# BUFFER.net
KiCad netlist of a schematic drawn in Altium Designer
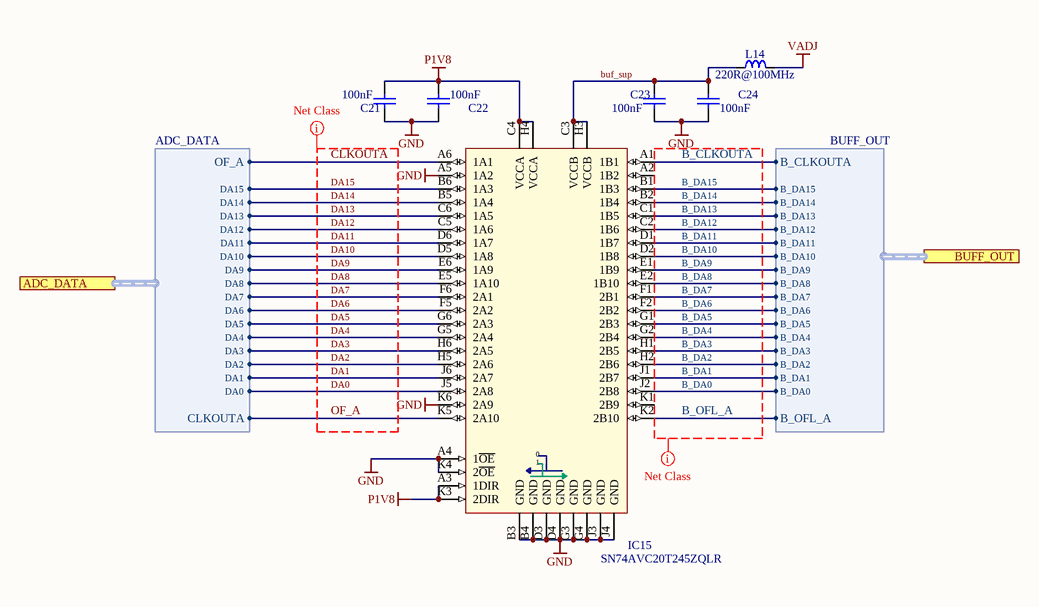
[diagram p0: BUFFER.SchDoc]

(export (version "E")
  (design (tool "Eeschema 10.0.6"))
  (components
    (comp (ref "C21")
      (value "100nF")
      (footprint "CAPC0603X33N")
      (description "Non-polarised capacitor")
      (fields
        (field (name "PART NUMBER") "CC0201_100NF_6.3V_10%_X5R")
        (field (name "VOLTAGE") "6.3V")
        (field (name "AUTHOR") "CERN DEM JLC")
      )
      (libsource (lib "Capacitors") (part "Capacitor - non polarized"))
    )
    (comp (ref "C22")
      (value "100nF")
      (footprint "CAPC0603X33N")
      (description "Non-polarised capacitor")
      (fields
        (field (name "PART NUMBER") "CC0201_100NF_6.3V_10%_X5R")
        (field (name "VOLTAGE") "6.3V")
        (field (name "AUTHOR") "CERN DEM JLC")
      )
      (libsource (lib "Capacitors") (part "Capacitor - non polarized"))
    )
    (comp (ref "C23")
      (value "100nF")
      (footprint "CAPC0603X33N")
      (description "Non-polarised capacitor")
      (fields
        (field (name "PART NUMBER") "CC0201_100NF_6.3V_10%_X5R")
        (field (name "VOLTAGE") "6.3V")
        (field (name "AUTHOR") "CERN DEM JLC")
      )
      (libsource (lib "Capacitors") (part "Capacitor - non polarized"))
    )
    (comp (ref "C24")
      (value "100nF")
      (footprint "CAPC0603X33N")
      (description "Non-polarised capacitor")
      (fields
        (field (name "PART NUMBER") "CC0201_100NF_6.3V_10%_X5R")
        (field (name "VOLTAGE") "6.3V")
        (field (name "AUTHOR") "CERN DEM JLC")
      )
      (libsource (lib "Capacitors") (part "Capacitor - non polarized"))
    )
    (comp (ref "IC15")
      (value "SN74AVC20T245ZQLR")
      (footprint "ZQL56(R-PBGA-N56)")
      (description "20-BIT DUAL SUPPLY BUS TRANSCEIVER")
      (libsource (lib "LIBRARY_SCH") (part "74AVC20T245"))
    )
    (comp (ref "L14")
      (value "220R@100MHz")
      (footprint "INDC2012X105N")
      (description "Inductor")
      (fields
        (field (name "PART NUMBER") "IND0805_MURATA_BLM21PG221SN1D")
        (field (name "POWER") "2A")
        (field (name "AUTHOR") "CERN DEM JLC")
      )
      (libsource (lib "Inductors & Transformers") (part "Inductor"))
    )
  )
  (nets
    (net (code "3") (name "/B_CLKOUTA") (class "Default")
      (node (ref "IC15") (pin "A1") (pinfunction "1B1_A1") (pintype "bidirectional"))
    )
    (net (code "4") (name "/B_DA0") (class "Default")
      (node (ref "IC15") (pin "J2") (pinfunction "2B8_J2") (pintype "bidirectional"))
    )
    (net (code "5") (name "/B_DA1") (class "Default")
      (node (ref "IC15") (pin "J1") (pinfunction "2B7_J1") (pintype "bidirectional"))
    )
    (net (code "6") (name "/B_DA2") (class "Default")
      (node (ref "IC15") (pin "H2") (pinfunction "2B6_H2") (pintype "bidirectional"))
    )
    (net (code "7") (name "/B_DA3") (class "Default")
      (node (ref "IC15") (pin "H1") (pinfunction "2B5_H1") (pintype "bidirectional"))
    )
    (net (code "8") (name "/B_DA4") (class "Default")
      (node (ref "IC15") (pin "G2") (pinfunction "2B4_G2") (pintype "bidirectional"))
    )
    (net (code "9") (name "/B_DA5") (class "Default")
      (node (ref "IC15") (pin "G1") (pinfunction "2B3_G1") (pintype "bidirectional"))
    )
    (net (code "10") (name "/B_DA6") (class "Default")
      (node (ref "IC15") (pin "F2") (pinfunction "2B2_F2") (pintype "bidirectional"))
    )
    (net (code "11") (name "/B_DA7") (class "Default")
      (node (ref "IC15") (pin "F1") (pinfunction "2B1_F1") (pintype "bidirectional"))
    )
    (net (code "12") (name "/B_DA8") (class "Default")
      (node (ref "IC15") (pin "E2") (pinfunction "1B10_E2") (pintype "bidirectional"))
    )
    (net (code "13") (name "/B_DA9") (class "Default")
      (node (ref "IC15") (pin "E1") (pinfunction "1B9_E1") (pintype "bidirectional"))
    )
    (net (code "14") (name "/B_DA10") (class "Default")
      (node (ref "IC15") (pin "D2") (pinfunction "1B8_D2") (pintype "bidirectional"))
    )
    (net (code "15") (name "/B_DA11") (class "Default")
      (node (ref "IC15") (pin "D1") (pinfunction "1B7_D1") (pintype "bidirectional"))
    )
    (net (code "16") (name "/B_DA12") (class "Default")
      (node (ref "IC15") (pin "C2") (pinfunction "1B6_C2") (pintype "bidirectional"))
    )
    (net (code "17") (name "/B_DA13") (class "Default")
      (node (ref "IC15") (pin "C1") (pinfunction "1B5_C1") (pintype "bidirectional"))
    )
    (net (code "18") (name "/B_DA14") (class "Default")
      (node (ref "IC15") (pin "B2") (pinfunction "1B4_B2") (pintype "bidirectional"))
    )
    (net (code "19") (name "/B_DA15") (class "Default")
      (node (ref "IC15") (pin "B1") (pinfunction "1B3_B1") (pintype "bidirectional"))
    )
    (net (code "20") (name "/B_OFL_A") (class "Default")
      (node (ref "IC15") (pin "K2") (pinfunction "2B10_K2") (pintype "bidirectional"))
    )
    (net (code "21") (name "/CLKOUTA") (class "Default")
      (node (ref "IC15") (pin "A6") (pinfunction "1A1_A6") (pintype "bidirectional"))
    )
    (net (code "22") (name "/DA0") (class "Default")
      (node (ref "IC15") (pin "J5") (pinfunction "2A8_J5") (pintype "bidirectional"))
    )
    (net (code "23") (name "/DA1") (class "Default")
      (node (ref "IC15") (pin "J6") (pinfunction "2A7_J6") (pintype "bidirectional"))
    )
    (net (code "24") (name "/DA2") (class "Default")
      (node (ref "IC15") (pin "H5") (pinfunction "2A6_H5") (pintype "bidirectional"))
    )
    (net (code "25") (name "/DA3") (class "Default")
      (node (ref "IC15") (pin "H6") (pinfunction "2A5_H6") (pintype "bidirectional"))
    )
    (net (code "26") (name "/DA4") (class "Default")
      (node (ref "IC15") (pin "G5") (pinfunction "2A4_G5") (pintype "bidirectional"))
    )
    (net (code "27") (name "/DA5") (class "Default")
      (node (ref "IC15") (pin "G6") (pinfunction "2A3_G6") (pintype "bidirectional"))
    )
    (net (code "28") (name "/DA6") (class "Default")
      (node (ref "IC15") (pin "F5") (pinfunction "2A2_F5") (pintype "bidirectional"))
    )
    (net (code "29") (name "/DA7") (class "Default")
      (node (ref "IC15") (pin "F6") (pinfunction "2A1_F6") (pintype "bidirectional"))
    )
    (net (code "30") (name "/DA8") (class "Default")
      (node (ref "IC15") (pin "E5") (pinfunction "1A10_E5") (pintype "bidirectional"))
    )
    (net (code "31") (name "/DA9") (class "Default")
      (node (ref "IC15") (pin "E6") (pinfunction "1A9_E6") (pintype "bidirectional"))
    )
    (net (code "32") (name "/DA10") (class "Default")
      (node (ref "IC15") (pin "D5") (pinfunction "1A8_D5") (pintype "bidirectional"))
    )
    (net (code "33") (name "/DA11") (class "Default")
      (node (ref "IC15") (pin "D6") (pinfunction "1A7_D6") (pintype "bidirectional"))
    )
    (net (code "34") (name "/DA12") (class "Default")
      (node (ref "IC15") (pin "C5") (pinfunction "1A6_C5") (pintype "bidirectional"))
    )
    (net (code "35") (name "/DA13") (class "Default")
      (node (ref "IC15") (pin "C6") (pinfunction "1A5_C6") (pintype "bidirectional"))
    )
    (net (code "36") (name "/DA14") (class "Default")
      (node (ref "IC15") (pin "B5") (pinfunction "1A4_B5") (pintype "bidirectional"))
    )
    (net (code "37") (name "/DA15") (class "Default")
      (node (ref "IC15") (pin "B6") (pinfunction "1A3_B6") (pintype "bidirectional"))
    )
    (net (code "38") (name "/OF_A") (class "Default")
      (node (ref "IC15") (pin "K5") (pinfunction "2A10_K5") (pintype "bidirectional"))
    )
    (net (code "39") (name "/buf_sup") (class "Default")
      (node (ref "C23") (pin "2") (pinfunction "2_2") (pintype "passive"))
      (node (ref "C24") (pin "2") (pinfunction "2_2") (pintype "passive"))
      (node (ref "IC15") (pin "C3") (pinfunction "VCCB_C3") (pintype "power_in"))
      (node (ref "IC15") (pin "H3") (pinfunction "VCCB_H3") (pintype "power_in"))
      (node (ref "L14") (pin "1") (pinfunction "1_1") (pintype "passive"))
    )
    (net (code "42") (name "GND") (class "Default")
      (node (ref "C21") (pin "1") (pinfunction "1_1") (pintype "passive"))
      (node (ref "C22") (pin "1") (pinfunction "1_1") (pintype "passive"))
      (node (ref "C23") (pin "1") (pinfunction "1_1") (pintype "passive"))
      (node (ref "C24") (pin "1") (pinfunction "1_1") (pintype "passive"))
      (node (ref "IC15") (pin "A4") (pinfunction "1~{OE}_A4") (pintype "input"))
      (node (ref "IC15") (pin "A5") (pinfunction "1A2_A5") (pintype "bidirectional"))
      (node (ref "IC15") (pin "B3") (pinfunction "GND_B3") (pintype "power_in"))
      (node (ref "IC15") (pin "B4") (pinfunction "GND_B4") (pintype "power_in"))
      (node (ref "IC15") (pin "D3") (pinfunction "GND_D3") (pintype "power_in"))
      (node (ref "IC15") (pin "D4") (pinfunction "GND_D4") (pintype "power_in"))
      (node (ref "IC15") (pin "G3") (pinfunction "GND_G3") (pintype "power_in"))
      (node (ref "IC15") (pin "G4") (pinfunction "GND_G4") (pintype "power_in"))
      (node (ref "IC15") (pin "J3") (pinfunction "GND_J3") (pintype "power_in"))
      (node (ref "IC15") (pin "J4") (pinfunction "GND_J4") (pintype "power_in"))
      (node (ref "IC15") (pin "K4") (pinfunction "2~{OE}_K4") (pintype "input"))
      (node (ref "IC15") (pin "K6") (pinfunction "2A9_K6") (pintype "bidirectional"))
    )
    (net (code "43") (name "P1V8") (class "Default")
      (node (ref "C21") (pin "2") (pinfunction "2_2") (pintype "passive"))
      (node (ref "C22") (pin "2") (pinfunction "2_2") (pintype "passive"))
      (node (ref "IC15") (pin "A3") (pinfunction "1DIR_A3") (pintype "input"))
      (node (ref "IC15") (pin "C4") (pinfunction "VCCA_C4") (pintype "power_in"))
      (node (ref "IC15") (pin "H4") (pinfunction "VCCA_H4") (pintype "power_in"))
      (node (ref "IC15") (pin "K3") (pinfunction "2DIR_K3") (pintype "input"))
    )
    (net (code "44") (name "VADJ") (class "Default")
      (node (ref "L14") (pin "2") (pinfunction "2_2") (pintype "passive"))
    )
    (net (code "45") (name "unconnected-(IC15-1B2-PadA2)") (class "Default")
      (node (ref "IC15") (pin "A2") (pinfunction "1B2_A2") (pintype "bidirectional"))
    )
    (net (code "46") (name "unconnected-(IC15-2B9-PadK1)") (class "Default")
      (node (ref "IC15") (pin "K1") (pinfunction "2B9_K1") (pintype "bidirectional"))
    )
  )
)
